# DC_DC_Power_Supply.net
KiCad netlist of a schematic drawn in Altium Designer
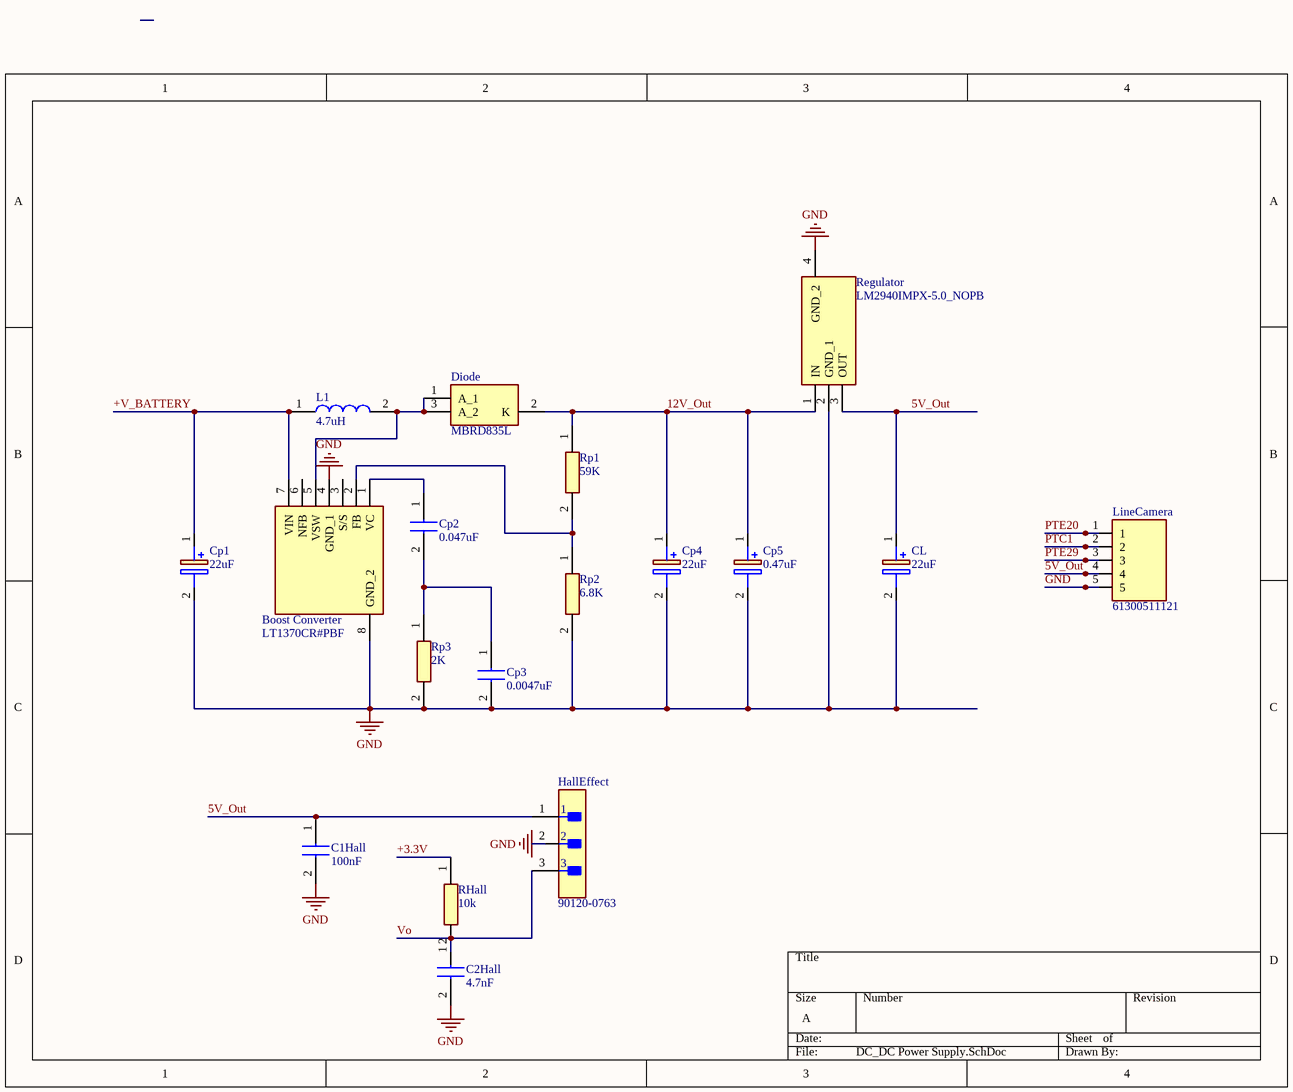
[diagram p0: DC_DC Power Supply.SchDoc]

(export (version "E")
  (design (tool "Eeschema 10.0.6"))
  (components
    (comp (ref "Boost Converter")
      (value "LT1370CR#PBF")
      (footprint "SamacSys:LT1370CRPBF")
      (description "12V Boost Converter")
      (fields (field (name "MOUSER PART NUMBER") "584-LT1370CR#PBF"))
      (libsource (lib "*") (part "LT1370CR#PBF"))
    )
    (comp (ref "C1Hall")
      (value "100nF")
      (footprint "SamacSys:CAPC5750X450N")
      (description "Capacitor")
      (fields
        (field (name "MANUFACTURER_PART_NUMBER") "2220Y2K00104KXRWS3")
        (field (name "MOUSER PART NUMBER") "843-2220Y2K104KXRWS2")
      )
      (libsource (lib "*") (part "2220Y2K00104KXRWS3"))
    )
    (comp (ref "C2Hall")
      (value "4.7nF")
      (footprint "SamacSys:C1812")
      (description "Capacitor")
      (fields
        (field (name "MANUFACTURER_PART_NUMBER") "C1812C472KGRACAUTO")
        (field (name "MOUSER PART NUMBER") "80-C1812C472KGRAUTO")
      )
      (libsource (lib "*") (part "C1812C472KGRACAUTO"))
    )
    (comp (ref "CL")
      (value "22uF")
      (footprint "SamacSys:CAPAE430X550N")
      (description "Capacitor Polarised")
      (fields
        (field (name "MANUFACTURER_PART_NUMBER") "UWP1HR22MCL1GB")
        (field (name "MOUSER PART NUMBER") "647-UWP1HR22MCL")
      )
      (libsource (lib "*") (part "UWP1HR22MCL1GB"))
    )
    (comp (ref "Cp1")
      (value "22uF")
      (footprint "SamacSys:CAPAE430X550N")
      (description "Capacitor Polarised")
      (fields
        (field (name "MANUFACTURER_PART_NUMBER") "UWP1HR22MCL1GB")
        (field (name "MOUSER PART NUMBER") "647-UWP1HR22MCL")
      )
      (libsource (lib "*") (part "UWP1HR22MCL1GB"))
    )
    (comp (ref "Cp2")
      (value "0.047uF")
      (footprint "SamacSys:CAPC0603X33N")
      (description "Capacitor")
      (fields
        (field (name "MANUFACTURER_PART_NUMBER") "GRM033R61C473KE84D")
        (field (name "MOUSER PART NUMBER") "81-GRM033R61C473KE4D")
      )
      (libsource (lib "*") (part "GRM033R61C473KE84D"))
    )
    (comp (ref "Cp3")
      (value "0.0047uF")
      (footprint "SamacSys:CAPC0603X33N")
      (description "Capacitor")
      (fields
        (field (name "MANUFACTURER_PART_NUMBER") "GRM033R71A472KA01D")
        (field (name "MOUSER PART NUMBER") "81-GRM033R71A472KA1D")
      )
      (libsource (lib "*") (part "GRM033R71A472KA01D"))
    )
    (comp (ref "Cp4")
      (value "22uF")
      (footprint "SamacSys:CAPAE430X550N")
      (description "Capacitor Polarised")
      (fields
        (field (name "MANUFACTURER_PART_NUMBER") "UWP1HR22MCL1GB")
        (field (name "MOUSER PART NUMBER") "647-UWP1HR22MCL")
      )
      (libsource (lib "*") (part "UWP1HR22MCL1GB"))
    )
    (comp (ref "Cp5")
      (value "0.47uF")
      (footprint "SamacSys:CAPAE430X550N")
      (description "Capacitor Polarised")
      (fields
        (field (name "MANUFACTURER_PART_NUMBER") "865230640004")
        (field (name "MOUSER PART NUMBER") "710-865230640004")
      )
      (libsource (lib "*") (part "865230640004"))
    )
    (comp (ref "Diode")
      (value "MBRD835L")
      (footprint "SamacSys:MBRD835L")
      (description "Diode")
      (fields (field (name "MOUSER PART NUMBER") "863-MBRD835L"))
      (libsource (lib "*") (part "MBRD835L"))
    )
    (comp (ref "HallEffect")
      (value "90120-0763")
      (footprint "FP-90120-0763-MFG")
      (description "CONN HEADER VERT 3POS 2.54MM")
      (fields
        (field (name "MANUFACTURER") "Molex")
        (field (name "OCTOPART") "https://octopart.com/90120-0763-molex-655433")
      )
      (libsource (lib "Altium Content Vault") (part "0d3f023dd272f625e17a2be33dea85f"))
    )
    (comp (ref "L1")
      (value "4.7uH")
      (footprint "SamacSys:ETQ-P4M_KFM")
      (description "Inductor")
      (fields
        (field (name "MANUFACTURER_PART_NUMBER") "ETQ-P4M4R7KFM")
        (field (name "MOUSER PART NUMBER") "667-ETQ-P4M4R7KFM")
      )
      (libsource (lib "*") (part "ETQ-P4M4R7KFM"))
    )
    (comp (ref "LineCamera")
      (value "61300511121")
      (footprint "SamacSys:HDRV5W64P0X254_1X5_1270X254X854P")
      (description "Connector")
      (fields (field (name "MOUSER PART NUMBER") "710-61300511121"))
      (libsource (lib "*") (part "61300511121"))
    )
    (comp (ref "Regulator")
      (value "LM2940IMPX-5.0_NOPB")
      (footprint "SamacSys:SOT230P700X180-4N")
      (description "Integrated Circuit")
      (fields
        (field (name "MANUFACTURER_PART_NUMBER") "LM2940IMPX-5.0/NOPB")
        (field (name "MOUSER PART NUMBER") "926-LM2940IMPX50NOPB")
      )
      (libsource (lib "*") (part "LM2940IMPX-5.0_NOPB"))
    )
    (comp (ref "RHall")
      (value "10k")
      (footprint "SamacSys:RESC1005X40N")
      (description "Resistor")
      (fields
        (field (name "MANUFACTURER_PART_NUMBER") "RC0402JR-0710KL")
        (field (name "MOUSER PART NUMBER") "603-RC0402JR-0710KL")
      )
      (libsource (lib "*") (part "RC0402JR-0710KL"))
    )
    (comp (ref "Rp1")
      (value "59K")
      (footprint "SamacSys:ERJ2RKD1004X")
      (description "Resistor")
      (fields
        (field (name "MANUFACTURER_PART_NUMBER") "ERJ-2RKF5902X")
        (field (name "MOUSER PART NUMBER") "667-ERJ-2RKF5902X")
      )
      (libsource (lib "*") (part "ERJ-2RKF5902X"))
    )
    (comp (ref "Rp2")
      (value "6.8K")
      (footprint "SamacSys:RESC1608X55N")
      (description "Resistor")
      (fields
        (field (name "MANUFACTURER_PART_NUMBER") "RC0603FR-106K8L")
        (field (name "MOUSER PART NUMBER") "603-RC0603FR-106K8L")
      )
      (libsource (lib "*") (part "RC0603FR-106K8L"))
    )
    (comp (ref "Rp3")
      (value "2K")
      (footprint "SamacSys:ERJ2RKD1004X")
      (description "Resistor")
      (fields
        (field (name "MANUFACTURER_PART_NUMBER") "ERJ-2RKF2001X")
        (field (name "MOUSER PART NUMBER") "667-ERJ-2RKF2001X")
      )
      (libsource (lib "*") (part "ERJ-2RKF2001X"))
    )
  )
  (nets
    (net (code "1") (name "/+3.3V") (class "Default")
      (node (ref "RHall") (pin "1") (pinfunction "1_1") (pintype "passive"))
    )
    (net (code "2") (name "/+V_BATTERY") (class "Default")
      (node (ref "Boost Converter") (pin "7") (pinfunction "VIN_7") (pintype "passive"))
      (node (ref "Cp1") (pin "1") (pinfunction "+_1") (pintype "passive"))
      (node (ref "L1") (pin "1") (pinfunction "1_1") (pintype "passive"))
    )
    (net (code "3") (name "/5V_Out") (class "Default")
      (node (ref "C1Hall") (pin "1") (pinfunction "1_1") (pintype "passive"))
      (node (ref "CL") (pin "1") (pinfunction "+_1") (pintype "passive"))
      (node (ref "HallEffect") (pin "1") (pinfunction "1_1") (pintype "passive"))
      (node (ref "LineCamera") (pin "4") (pinfunction "4_4") (pintype "passive"))
      (node (ref "Regulator") (pin "3") (pinfunction "OUT_3") (pintype "passive"))
    )
    (net (code "4") (name "/12V_Out") (class "Default")
      (node (ref "Cp4") (pin "1") (pinfunction "+_1") (pintype "passive"))
      (node (ref "Cp5") (pin "1") (pinfunction "+_1") (pintype "passive"))
      (node (ref "Diode") (pin "2") (pinfunction "K_2") (pintype "passive"))
      (node (ref "Regulator") (pin "1") (pinfunction "IN_1") (pintype "passive"))
      (node (ref "Rp1") (pin "1") (pinfunction "1_1") (pintype "passive"))
    )
    (net (code "5") (name "/PTC1") (class "Default")
      (node (ref "LineCamera") (pin "2") (pinfunction "2_2") (pintype "passive"))
    )
    (net (code "6") (name "/PTE20") (class "Default")
      (node (ref "LineCamera") (pin "1") (pinfunction "1_1") (pintype "passive"))
    )
    (net (code "7") (name "/PTE29") (class "Default")
      (node (ref "LineCamera") (pin "3") (pinfunction "3_3") (pintype "passive"))
    )
    (net (code "8") (name "/Vo") (class "Default")
      (node (ref "C2Hall") (pin "1") (pinfunction "1_1") (pintype "passive"))
      (node (ref "HallEffect") (pin "3") (pinfunction "3_3") (pintype "passive"))
      (node (ref "RHall") (pin "2") (pinfunction "2_2") (pintype "passive"))
    )
    (net (code "9") (name "GND") (class "Default")
      (node (ref "Boost Converter") (pin "4") (pinfunction "GND_1_4") (pintype "passive"))
      (node (ref "Boost Converter") (pin "8") (pinfunction "GND_2_8") (pintype "passive"))
      (node (ref "C1Hall") (pin "2") (pinfunction "2_2") (pintype "passive"))
      (node (ref "C2Hall") (pin "2") (pinfunction "2_2") (pintype "passive"))
      (node (ref "CL") (pin "2") (pinfunction "-_2") (pintype "passive"))
      (node (ref "Cp1") (pin "2") (pinfunction "-_2") (pintype "passive"))
      (node (ref "Cp3") (pin "2") (pinfunction "2_2") (pintype "passive"))
      (node (ref "Cp4") (pin "2") (pinfunction "-_2") (pintype "passive"))
      (node (ref "Cp5") (pin "2") (pinfunction "-_2") (pintype "passive"))
      (node (ref "HallEffect") (pin "2") (pinfunction "2_2") (pintype "passive"))
      (node (ref "LineCamera") (pin "5") (pinfunction "5_5") (pintype "passive"))
      (node (ref "Regulator") (pin "2") (pinfunction "GND_1_2") (pintype "passive"))
      (node (ref "Regulator") (pin "4") (pinfunction "GND_2_4") (pintype "passive"))
      (node (ref "Rp2") (pin "2") (pinfunction "2_2") (pintype "passive"))
      (node (ref "Rp3") (pin "2") (pinfunction "2_2") (pintype "passive"))
    )
    (net (code "10") (name "Net-(Boost Converter-FB)") (class "Default")
      (node (ref "Boost Converter") (pin "2") (pinfunction "FB_2") (pintype "passive"))
      (node (ref "Rp1") (pin "2") (pinfunction "2_2") (pintype "passive"))
      (node (ref "Rp2") (pin "1") (pinfunction "1_1") (pintype "passive"))
    )
    (net (code "11") (name "Net-(Boost Converter-VC)") (class "Default")
      (node (ref "Boost Converter") (pin "1") (pinfunction "VC_1") (pintype "passive"))
      (node (ref "Cp2") (pin "1") (pinfunction "1_1") (pintype "passive"))
    )
    (net (code "12") (name "Net-(Boost Converter-VSW)") (class "Default")
      (node (ref "Boost Converter") (pin "5") (pinfunction "VSW_5") (pintype "passive"))
      (node (ref "Diode") (pin "1") (pinfunction "A_1_1") (pintype "passive"))
      (node (ref "Diode") (pin "3") (pinfunction "A_2_3") (pintype "passive"))
      (node (ref "L1") (pin "2") (pinfunction "2_2") (pintype "passive"))
    )
    (net (code "13") (name "Net-(Cp2-Pad2)") (class "Default")
      (node (ref "Cp2") (pin "2") (pinfunction "2_2") (pintype "passive"))
      (node (ref "Cp3") (pin "1") (pinfunction "1_1") (pintype "passive"))
      (node (ref "Rp3") (pin "1") (pinfunction "1_1") (pintype "passive"))
    )
    (net (code "14") (name "unconnected-(Boost Converter-NFB-Pad6)") (class "Default")
      (node (ref "Boost Converter") (pin "6") (pinfunction "NFB_6") (pintype "passive"))
    )
    (net (code "15") (name "unconnected-(Boost Converter-S{slash}S-Pad3)") (class "Default")
      (node (ref "Boost Converter") (pin "3") (pinfunction "S/S_3") (pintype "passive"))
    )
  )
)
